# Sheet1.net
KiCad netlist of a schematic drawn in Altium Designer
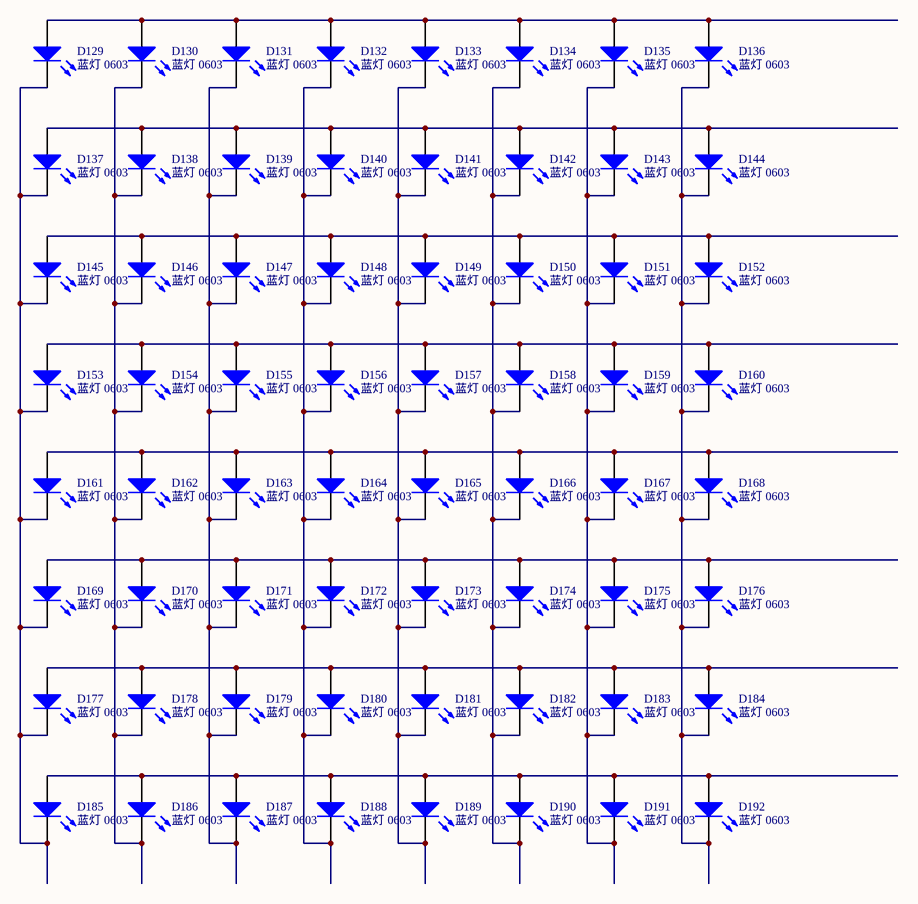
[diagram p0: Sheet1.SchDoc]

(export (version "E")
  (design (tool "Eeschema 10.0.6"))
  (components
    (comp (ref "D129")
      (value "蓝灯 0603")
      (footprint "0603_LED_S1")
      (description "发光二极管")
      (libsource (lib "Miscellaneous Devices LC") (part "0603 蓝灯"))
    )
    (comp (ref "D130")
      (value "蓝灯 0603")
      (footprint "0603_LED_S1")
      (description "发光二极管")
      (libsource (lib "Miscellaneous Devices LC") (part "0603 蓝灯"))
    )
    (comp (ref "D131")
      (value "蓝灯 0603")
      (footprint "0603_LED_S1")
      (description "发光二极管")
      (libsource (lib "Miscellaneous Devices LC") (part "0603 蓝灯"))
    )
    (comp (ref "D132")
      (value "蓝灯 0603")
      (footprint "0603_LED_S1")
      (description "发光二极管")
      (libsource (lib "Miscellaneous Devices LC") (part "0603 蓝灯"))
    )
    (comp (ref "D133")
      (value "蓝灯 0603")
      (footprint "0603_LED_S1")
      (description "发光二极管")
      (libsource (lib "Miscellaneous Devices LC") (part "0603 蓝灯"))
    )
    (comp (ref "D134")
      (value "蓝灯 0603")
      (footprint "0603_LED_S1")
      (description "发光二极管")
      (libsource (lib "Miscellaneous Devices LC") (part "0603 蓝灯"))
    )
    (comp (ref "D135")
      (value "蓝灯 0603")
      (footprint "0603_LED_S1")
      (description "发光二极管")
      (libsource (lib "Miscellaneous Devices LC") (part "0603 蓝灯"))
    )
    (comp (ref "D136")
      (value "蓝灯 0603")
      (footprint "0603_LED_S1")
      (description "发光二极管")
      (libsource (lib "Miscellaneous Devices LC") (part "0603 蓝灯"))
    )
    (comp (ref "D137")
      (value "蓝灯 0603")
      (footprint "0603_LED_S1")
      (description "发光二极管")
      (libsource (lib "Miscellaneous Devices LC") (part "0603 蓝灯"))
    )
    (comp (ref "D138")
      (value "蓝灯 0603")
      (footprint "0603_LED_S1")
      (description "发光二极管")
      (libsource (lib "Miscellaneous Devices LC") (part "0603 蓝灯"))
    )
    (comp (ref "D139")
      (value "蓝灯 0603")
      (footprint "0603_LED_S1")
      (description "发光二极管")
      (libsource (lib "Miscellaneous Devices LC") (part "0603 蓝灯"))
    )
    (comp (ref "D140")
      (value "蓝灯 0603")
      (footprint "0603_LED_S1")
      (description "发光二极管")
      (libsource (lib "Miscellaneous Devices LC") (part "0603 蓝灯"))
    )
    (comp (ref "D141")
      (value "蓝灯 0603")
      (footprint "0603_LED_S1")
      (description "发光二极管")
      (libsource (lib "Miscellaneous Devices LC") (part "0603 蓝灯"))
    )
    (comp (ref "D142")
      (value "蓝灯 0603")
      (footprint "0603_LED_S1")
      (description "发光二极管")
      (libsource (lib "Miscellaneous Devices LC") (part "0603 蓝灯"))
    )
    (comp (ref "D143")
      (value "蓝灯 0603")
      (footprint "0603_LED_S1")
      (description "发光二极管")
      (libsource (lib "Miscellaneous Devices LC") (part "0603 蓝灯"))
    )
    (comp (ref "D144")
      (value "蓝灯 0603")
      (footprint "0603_LED_S1")
      (description "发光二极管")
      (libsource (lib "Miscellaneous Devices LC") (part "0603 蓝灯"))
    )
    (comp (ref "D145")
      (value "蓝灯 0603")
      (footprint "0603_LED_S1")
      (description "发光二极管")
      (libsource (lib "Miscellaneous Devices LC") (part "0603 蓝灯"))
    )
    (comp (ref "D146")
      (value "蓝灯 0603")
      (footprint "0603_LED_S1")
      (description "发光二极管")
      (libsource (lib "Miscellaneous Devices LC") (part "0603 蓝灯"))
    )
    (comp (ref "D147")
      (value "蓝灯 0603")
      (footprint "0603_LED_S1")
      (description "发光二极管")
      (libsource (lib "Miscellaneous Devices LC") (part "0603 蓝灯"))
    )
    (comp (ref "D148")
      (value "蓝灯 0603")
      (footprint "0603_LED_S1")
      (description "发光二极管")
      (libsource (lib "Miscellaneous Devices LC") (part "0603 蓝灯"))
    )
    (comp (ref "D149")
      (value "蓝灯 0603")
      (footprint "0603_LED_S1")
      (description "发光二极管")
      (libsource (lib "Miscellaneous Devices LC") (part "0603 蓝灯"))
    )
    (comp (ref "D150")
      (value "蓝灯 0603")
      (footprint "0603_LED_S1")
      (description "发光二极管")
      (libsource (lib "Miscellaneous Devices LC") (part "0603 蓝灯"))
    )
    (comp (ref "D151")
      (value "蓝灯 0603")
      (footprint "0603_LED_S1")
      (description "发光二极管")
      (libsource (lib "Miscellaneous Devices LC") (part "0603 蓝灯"))
    )
    (comp (ref "D152")
      (value "蓝灯 0603")
      (footprint "0603_LED_S1")
      (description "发光二极管")
      (libsource (lib "Miscellaneous Devices LC") (part "0603 蓝灯"))
    )
    (comp (ref "D153")
      (value "蓝灯 0603")
      (footprint "0603_LED_S1")
      (description "发光二极管")
      (libsource (lib "Miscellaneous Devices LC") (part "0603 蓝灯"))
    )
    (comp (ref "D154")
      (value "蓝灯 0603")
      (footprint "0603_LED_S1")
      (description "发光二极管")
      (libsource (lib "Miscellaneous Devices LC") (part "0603 蓝灯"))
    )
    (comp (ref "D155")
      (value "蓝灯 0603")
      (footprint "0603_LED_S1")
      (description "发光二极管")
      (libsource (lib "Miscellaneous Devices LC") (part "0603 蓝灯"))
    )
    (comp (ref "D156")
      (value "蓝灯 0603")
      (footprint "0603_LED_S1")
      (description "发光二极管")
      (libsource (lib "Miscellaneous Devices LC") (part "0603 蓝灯"))
    )
    (comp (ref "D157")
      (value "蓝灯 0603")
      (footprint "0603_LED_S1")
      (description "发光二极管")
      (libsource (lib "Miscellaneous Devices LC") (part "0603 蓝灯"))
    )
    (comp (ref "D158")
      (value "蓝灯 0603")
      (footprint "0603_LED_S1")
      (description "发光二极管")
      (libsource (lib "Miscellaneous Devices LC") (part "0603 蓝灯"))
    )
    (comp (ref "D159")
      (value "蓝灯 0603")
      (footprint "0603_LED_S1")
      (description "发光二极管")
      (libsource (lib "Miscellaneous Devices LC") (part "0603 蓝灯"))
    )
    (comp (ref "D160")
      (value "蓝灯 0603")
      (footprint "0603_LED_S1")
      (description "发光二极管")
      (libsource (lib "Miscellaneous Devices LC") (part "0603 蓝灯"))
    )
    (comp (ref "D161")
      (value "蓝灯 0603")
      (footprint "0603_LED_S1")
      (description "发光二极管")
      (libsource (lib "Miscellaneous Devices LC") (part "0603 蓝灯"))
    )
    (comp (ref "D162")
      (value "蓝灯 0603")
      (footprint "0603_LED_S1")
      (description "发光二极管")
      (libsource (lib "Miscellaneous Devices LC") (part "0603 蓝灯"))
    )
    (comp (ref "D163")
      (value "蓝灯 0603")
      (footprint "0603_LED_S1")
      (description "发光二极管")
      (libsource (lib "Miscellaneous Devices LC") (part "0603 蓝灯"))
    )
    (comp (ref "D164")
      (value "蓝灯 0603")
      (footprint "0603_LED_S1")
      (description "发光二极管")
      (libsource (lib "Miscellaneous Devices LC") (part "0603 蓝灯"))
    )
    (comp (ref "D165")
      (value "蓝灯 0603")
      (footprint "0603_LED_S1")
      (description "发光二极管")
      (libsource (lib "Miscellaneous Devices LC") (part "0603 蓝灯"))
    )
    (comp (ref "D166")
      (value "蓝灯 0603")
      (footprint "0603_LED_S1")
      (description "发光二极管")
      (libsource (lib "Miscellaneous Devices LC") (part "0603 蓝灯"))
    )
    (comp (ref "D167")
      (value "蓝灯 0603")
      (footprint "0603_LED_S1")
      (description "发光二极管")
      (libsource (lib "Miscellaneous Devices LC") (part "0603 蓝灯"))
    )
    (comp (ref "D168")
      (value "蓝灯 0603")
      (footprint "0603_LED_S1")
      (description "发光二极管")
      (libsource (lib "Miscellaneous Devices LC") (part "0603 蓝灯"))
    )
    (comp (ref "D169")
      (value "蓝灯 0603")
      (footprint "0603_LED_S1")
      (description "发光二极管")
      (libsource (lib "Miscellaneous Devices LC") (part "0603 蓝灯"))
    )
    (comp (ref "D170")
      (value "蓝灯 0603")
      (footprint "0603_LED_S1")
      (description "发光二极管")
      (libsource (lib "Miscellaneous Devices LC") (part "0603 蓝灯"))
    )
    (comp (ref "D171")
      (value "蓝灯 0603")
      (footprint "0603_LED_S1")
      (description "发光二极管")
      (libsource (lib "Miscellaneous Devices LC") (part "0603 蓝灯"))
    )
    (comp (ref "D172")
      (value "蓝灯 0603")
      (footprint "0603_LED_S1")
      (description "发光二极管")
      (libsource (lib "Miscellaneous Devices LC") (part "0603 蓝灯"))
    )
    (comp (ref "D173")
      (value "蓝灯 0603")
      (footprint "0603_LED_S1")
      (description "发光二极管")
      (libsource (lib "Miscellaneous Devices LC") (part "0603 蓝灯"))
    )
    (comp (ref "D174")
      (value "蓝灯 0603")
      (footprint "0603_LED_S1")
      (description "发光二极管")
      (libsource (lib "Miscellaneous Devices LC") (part "0603 蓝灯"))
    )
    (comp (ref "D175")
      (value "蓝灯 0603")
      (footprint "0603_LED_S1")
      (description "发光二极管")
      (libsource (lib "Miscellaneous Devices LC") (part "0603 蓝灯"))
    )
    (comp (ref "D176")
      (value "蓝灯 0603")
      (footprint "0603_LED_S1")
      (description "发光二极管")
      (libsource (lib "Miscellaneous Devices LC") (part "0603 蓝灯"))
    )
    (comp (ref "D177")
      (value "蓝灯 0603")
      (footprint "0603_LED_S1")
      (description "发光二极管")
      (libsource (lib "Miscellaneous Devices LC") (part "0603 蓝灯"))
    )
    (comp (ref "D178")
      (value "蓝灯 0603")
      (footprint "0603_LED_S1")
      (description "发光二极管")
      (libsource (lib "Miscellaneous Devices LC") (part "0603 蓝灯"))
    )
    (comp (ref "D179")
      (value "蓝灯 0603")
      (footprint "0603_LED_S1")
      (description "发光二极管")
      (libsource (lib "Miscellaneous Devices LC") (part "0603 蓝灯"))
    )
    (comp (ref "D180")
      (value "蓝灯 0603")
      (footprint "0603_LED_S1")
      (description "发光二极管")
      (libsource (lib "Miscellaneous Devices LC") (part "0603 蓝灯"))
    )
    (comp (ref "D181")
      (value "蓝灯 0603")
      (footprint "0603_LED_S1")
      (description "发光二极管")
      (libsource (lib "Miscellaneous Devices LC") (part "0603 蓝灯"))
    )
    (comp (ref "D182")
      (value "蓝灯 0603")
      (footprint "0603_LED_S1")
      (description "发光二极管")
      (libsource (lib "Miscellaneous Devices LC") (part "0603 蓝灯"))
    )
    (comp (ref "D183")
      (value "蓝灯 0603")
      (footprint "0603_LED_S1")
      (description "发光二极管")
      (libsource (lib "Miscellaneous Devices LC") (part "0603 蓝灯"))
    )
    (comp (ref "D184")
      (value "蓝灯 0603")
      (footprint "0603_LED_S1")
      (description "发光二极管")
      (libsource (lib "Miscellaneous Devices LC") (part "0603 蓝灯"))
    )
    (comp (ref "D185")
      (value "蓝灯 0603")
      (footprint "0603_LED_S1")
      (description "发光二极管")
      (libsource (lib "Miscellaneous Devices LC") (part "0603 蓝灯"))
    )
    (comp (ref "D186")
      (value "蓝灯 0603")
      (footprint "0603_LED_S1")
      (description "发光二极管")
      (libsource (lib "Miscellaneous Devices LC") (part "0603 蓝灯"))
    )
    (comp (ref "D187")
      (value "蓝灯 0603")
      (footprint "0603_LED_S1")
      (description "发光二极管")
      (libsource (lib "Miscellaneous Devices LC") (part "0603 蓝灯"))
    )
    (comp (ref "D188")
      (value "蓝灯 0603")
      (footprint "0603_LED_S1")
      (description "发光二极管")
      (libsource (lib "Miscellaneous Devices LC") (part "0603 蓝灯"))
    )
    (comp (ref "D189")
      (value "蓝灯 0603")
      (footprint "0603_LED_S1")
      (description "发光二极管")
      (libsource (lib "Miscellaneous Devices LC") (part "0603 蓝灯"))
    )
    (comp (ref "D190")
      (value "蓝灯 0603")
      (footprint "0603_LED_S1")
      (description "发光二极管")
      (libsource (lib "Miscellaneous Devices LC") (part "0603 蓝灯"))
    )
    (comp (ref "D191")
      (value "蓝灯 0603")
      (footprint "0603_LED_S1")
      (description "发光二极管")
      (libsource (lib "Miscellaneous Devices LC") (part "0603 蓝灯"))
    )
    (comp (ref "D192")
      (value "蓝灯 0603")
      (footprint "0603_LED_S1")
      (description "发光二极管")
      (libsource (lib "Miscellaneous Devices LC") (part "0603 蓝灯"))
    )
  )
  (nets
    (net (code "1") (name "Net-(D129-PadA)") (class "Default")
      (node (ref "D129") (pin "A") (pinfunction "A_A") (pintype "passive"))
      (node (ref "D130") (pin "A") (pinfunction "A_A") (pintype "passive"))
      (node (ref "D131") (pin "A") (pinfunction "A_A") (pintype "passive"))
      (node (ref "D132") (pin "A") (pinfunction "A_A") (pintype "passive"))
      (node (ref "D133") (pin "A") (pinfunction "A_A") (pintype "passive"))
      (node (ref "D134") (pin "A") (pinfunction "A_A") (pintype "passive"))
      (node (ref "D135") (pin "A") (pinfunction "A_A") (pintype "passive"))
      (node (ref "D136") (pin "A") (pinfunction "A_A") (pintype "passive"))
    )
    (net (code "2") (name "Net-(D129-PadK)") (class "Default")
      (node (ref "D129") (pin "K") (pinfunction "K_K") (pintype "passive"))
      (node (ref "D137") (pin "K") (pinfunction "K_K") (pintype "passive"))
      (node (ref "D145") (pin "K") (pinfunction "K_K") (pintype "passive"))
      (node (ref "D153") (pin "K") (pinfunction "K_K") (pintype "passive"))
      (node (ref "D161") (pin "K") (pinfunction "K_K") (pintype "passive"))
      (node (ref "D169") (pin "K") (pinfunction "K_K") (pintype "passive"))
      (node (ref "D177") (pin "K") (pinfunction "K_K") (pintype "passive"))
      (node (ref "D185") (pin "K") (pinfunction "K_K") (pintype "passive"))
    )
    (net (code "3") (name "Net-(D130-PadK)") (class "Default")
      (node (ref "D130") (pin "K") (pinfunction "K_K") (pintype "passive"))
      (node (ref "D138") (pin "K") (pinfunction "K_K") (pintype "passive"))
      (node (ref "D146") (pin "K") (pinfunction "K_K") (pintype "passive"))
      (node (ref "D154") (pin "K") (pinfunction "K_K") (pintype "passive"))
      (node (ref "D162") (pin "K") (pinfunction "K_K") (pintype "passive"))
      (node (ref "D170") (pin "K") (pinfunction "K_K") (pintype "passive"))
      (node (ref "D178") (pin "K") (pinfunction "K_K") (pintype "passive"))
      (node (ref "D186") (pin "K") (pinfunction "K_K") (pintype "passive"))
    )
    (net (code "4") (name "Net-(D131-PadK)") (class "Default")
      (node (ref "D131") (pin "K") (pinfunction "K_K") (pintype "passive"))
      (node (ref "D139") (pin "K") (pinfunction "K_K") (pintype "passive"))
      (node (ref "D147") (pin "K") (pinfunction "K_K") (pintype "passive"))
      (node (ref "D155") (pin "K") (pinfunction "K_K") (pintype "passive"))
      (node (ref "D163") (pin "K") (pinfunction "K_K") (pintype "passive"))
      (node (ref "D171") (pin "K") (pinfunction "K_K") (pintype "passive"))
      (node (ref "D179") (pin "K") (pinfunction "K_K") (pintype "passive"))
      (node (ref "D187") (pin "K") (pinfunction "K_K") (pintype "passive"))
    )
    (net (code "5") (name "Net-(D132-PadK)") (class "Default")
      (node (ref "D132") (pin "K") (pinfunction "K_K") (pintype "passive"))
      (node (ref "D140") (pin "K") (pinfunction "K_K") (pintype "passive"))
      (node (ref "D148") (pin "K") (pinfunction "K_K") (pintype "passive"))
      (node (ref "D156") (pin "K") (pinfunction "K_K") (pintype "passive"))
      (node (ref "D164") (pin "K") (pinfunction "K_K") (pintype "passive"))
      (node (ref "D172") (pin "K") (pinfunction "K_K") (pintype "passive"))
      (node (ref "D180") (pin "K") (pinfunction "K_K") (pintype "passive"))
      (node (ref "D188") (pin "K") (pinfunction "K_K") (pintype "passive"))
    )
    (net (code "6") (name "Net-(D133-PadK)") (class "Default")
      (node (ref "D133") (pin "K") (pinfunction "K_K") (pintype "passive"))
      (node (ref "D141") (pin "K") (pinfunction "K_K") (pintype "passive"))
      (node (ref "D149") (pin "K") (pinfunction "K_K") (pintype "passive"))
      (node (ref "D157") (pin "K") (pinfunction "K_K") (pintype "passive"))
      (node (ref "D165") (pin "K") (pinfunction "K_K") (pintype "passive"))
      (node (ref "D173") (pin "K") (pinfunction "K_K") (pintype "passive"))
      (node (ref "D181") (pin "K") (pinfunction "K_K") (pintype "passive"))
      (node (ref "D189") (pin "K") (pinfunction "K_K") (pintype "passive"))
    )
    (net (code "7") (name "Net-(D134-PadK)") (class "Default")
      (node (ref "D134") (pin "K") (pinfunction "K_K") (pintype "passive"))
      (node (ref "D142") (pin "K") (pinfunction "K_K") (pintype "passive"))
      (node (ref "D150") (pin "K") (pinfunction "K_K") (pintype "passive"))
      (node (ref "D158") (pin "K") (pinfunction "K_K") (pintype "passive"))
      (node (ref "D166") (pin "K") (pinfunction "K_K") (pintype "passive"))
      (node (ref "D174") (pin "K") (pinfunction "K_K") (pintype "passive"))
      (node (ref "D182") (pin "K") (pinfunction "K_K") (pintype "passive"))
      (node (ref "D190") (pin "K") (pinfunction "K_K") (pintype "passive"))
    )
    (net (code "8") (name "Net-(D135-PadK)") (class "Default")
      (node (ref "D135") (pin "K") (pinfunction "K_K") (pintype "passive"))
      (node (ref "D143") (pin "K") (pinfunction "K_K") (pintype "passive"))
      (node (ref "D151") (pin "K") (pinfunction "K_K") (pintype "passive"))
      (node (ref "D159") (pin "K") (pinfunction "K_K") (pintype "passive"))
      (node (ref "D167") (pin "K") (pinfunction "K_K") (pintype "passive"))
      (node (ref "D175") (pin "K") (pinfunction "K_K") (pintype "passive"))
      (node (ref "D183") (pin "K") (pinfunction "K_K") (pintype "passive"))
      (node (ref "D191") (pin "K") (pinfunction "K_K") (pintype "passive"))
    )
    (net (code "9") (name "Net-(D136-PadK)") (class "Default")
      (node (ref "D136") (pin "K") (pinfunction "K_K") (pintype "passive"))
      (node (ref "D144") (pin "K") (pinfunction "K_K") (pintype "passive"))
      (node (ref "D152") (pin "K") (pinfunction "K_K") (pintype "passive"))
      (node (ref "D160") (pin "K") (pinfunction "K_K") (pintype "passive"))
      (node (ref "D168") (pin "K") (pinfunction "K_K") (pintype "passive"))
      (node (ref "D176") (pin "K") (pinfunction "K_K") (pintype "passive"))
      (node (ref "D184") (pin "K") (pinfunction "K_K") (pintype "passive"))
      (node (ref "D192") (pin "K") (pinfunction "K_K") (pintype "passive"))
    )
    (net (code "10") (name "Net-(D137-PadA)") (class "Default")
      (node (ref "D137") (pin "A") (pinfunction "A_A") (pintype "passive"))
      (node (ref "D138") (pin "A") (pinfunction "A_A") (pintype "passive"))
      (node (ref "D139") (pin "A") (pinfunction "A_A") (pintype "passive"))
      (node (ref "D140") (pin "A") (pinfunction "A_A") (pintype "passive"))
      (node (ref "D141") (pin "A") (pinfunction "A_A") (pintype "passive"))
      (node (ref "D142") (pin "A") (pinfunction "A_A") (pintype "passive"))
      (node (ref "D143") (pin "A") (pinfunction "A_A") (pintype "passive"))
      (node (ref "D144") (pin "A") (pinfunction "A_A") (pintype "passive"))
    )
    (net (code "11") (name "Net-(D145-PadA)") (class "Default")
      (node (ref "D145") (pin "A") (pinfunction "A_A") (pintype "passive"))
      (node (ref "D146") (pin "A") (pinfunction "A_A") (pintype "passive"))
      (node (ref "D147") (pin "A") (pinfunction "A_A") (pintype "passive"))
      (node (ref "D148") (pin "A") (pinfunction "A_A") (pintype "passive"))
      (node (ref "D149") (pin "A") (pinfunction "A_A") (pintype "passive"))
      (node (ref "D150") (pin "A") (pinfunction "A_A") (pintype "passive"))
      (node (ref "D151") (pin "A") (pinfunction "A_A") (pintype "passive"))
      (node (ref "D152") (pin "A") (pinfunction "A_A") (pintype "passive"))
    )
    (net (code "12") (name "Net-(D153-PadA)") (class "Default")
      (node (ref "D153") (pin "A") (pinfunction "A_A") (pintype "passive"))
      (node (ref "D154") (pin "A") (pinfunction "A_A") (pintype "passive"))
      (node (ref "D155") (pin "A") (pinfunction "A_A") (pintype "passive"))
      (node (ref "D156") (pin "A") (pinfunction "A_A") (pintype "passive"))
      (node (ref "D157") (pin "A") (pinfunction "A_A") (pintype "passive"))
      (node (ref "D158") (pin "A") (pinfunction "A_A") (pintype "passive"))
      (node (ref "D159") (pin "A") (pinfunction "A_A") (pintype "passive"))
      (node (ref "D160") (pin "A") (pinfunction "A_A") (pintype "passive"))
    )
    (net (code "13") (name "Net-(D161-PadA)") (class "Default")
      (node (ref "D161") (pin "A") (pinfunction "A_A") (pintype "passive"))
      (node (ref "D162") (pin "A") (pinfunction "A_A") (pintype "passive"))
      (node (ref "D163") (pin "A") (pinfunction "A_A") (pintype "passive"))
      (node (ref "D164") (pin "A") (pinfunction "A_A") (pintype "passive"))
      (node (ref "D165") (pin "A") (pinfunction "A_A") (pintype "passive"))
      (node (ref "D166") (pin "A") (pinfunction "A_A") (pintype "passive"))
      (node (ref "D167") (pin "A") (pinfunction "A_A") (pintype "passive"))
      (node (ref "D168") (pin "A") (pinfunction "A_A") (pintype "passive"))
    )
    (net (code "14") (name "Net-(D169-PadA)") (class "Default")
      (node (ref "D169") (pin "A") (pinfunction "A_A") (pintype "passive"))
      (node (ref "D170") (pin "A") (pinfunction "A_A") (pintype "passive"))
      (node (ref "D171") (pin "A") (pinfunction "A_A") (pintype "passive"))
      (node (ref "D172") (pin "A") (pinfunction "A_A") (pintype "passive"))
      (node (ref "D173") (pin "A") (pinfunction "A_A") (pintype "passive"))
      (node (ref "D174") (pin "A") (pinfunction "A_A") (pintype "passive"))
      (node (ref "D175") (pin "A") (pinfunction "A_A") (pintype "passive"))
      (node (ref "D176") (pin "A") (pinfunction "A_A") (pintype "passive"))
    )
    (net (code "15") (name "Net-(D177-PadA)") (class "Default")
      (node (ref "D177") (pin "A") (pinfunction "A_A") (pintype "passive"))
      (node (ref "D178") (pin "A") (pinfunction "A_A") (pintype "passive"))
      (node (ref "D179") (pin "A") (pinfunction "A_A") (pintype "passive"))
      (node (ref "D180") (pin "A") (pinfunction "A_A") (pintype "passive"))
      (node (ref "D181") (pin "A") (pinfunction "A_A") (pintype "passive"))
      (node (ref "D182") (pin "A") (pinfunction "A_A") (pintype "passive"))
      (node (ref "D183") (pin "A") (pinfunction "A_A") (pintype "passive"))
      (node (ref "D184") (pin "A") (pinfunction "A_A") (pintype "passive"))
    )
    (net (code "16") (name "Net-(D185-PadA)") (class "Default")
      (node (ref "D185") (pin "A") (pinfunction "A_A") (pintype "passive"))
      (node (ref "D186") (pin "A") (pinfunction "A_A") (pintype "passive"))
      (node (ref "D187") (pin "A") (pinfunction "A_A") (pintype "passive"))
      (node (ref "D188") (pin "A") (pinfunction "A_A") (pintype "passive"))
      (node (ref "D189") (pin "A") (pinfunction "A_A") (pintype "passive"))
      (node (ref "D190") (pin "A") (pinfunction "A_A") (pintype "passive"))
      (node (ref "D191") (pin "A") (pinfunction "A_A") (pintype "passive"))
      (node (ref "D192") (pin "A") (pinfunction "A_A") (pintype "passive"))
    )
  )
)
